# Teensy3_based_M_M_board_5x5.net
KiCad netlist of a schematic drawn in EAGLE
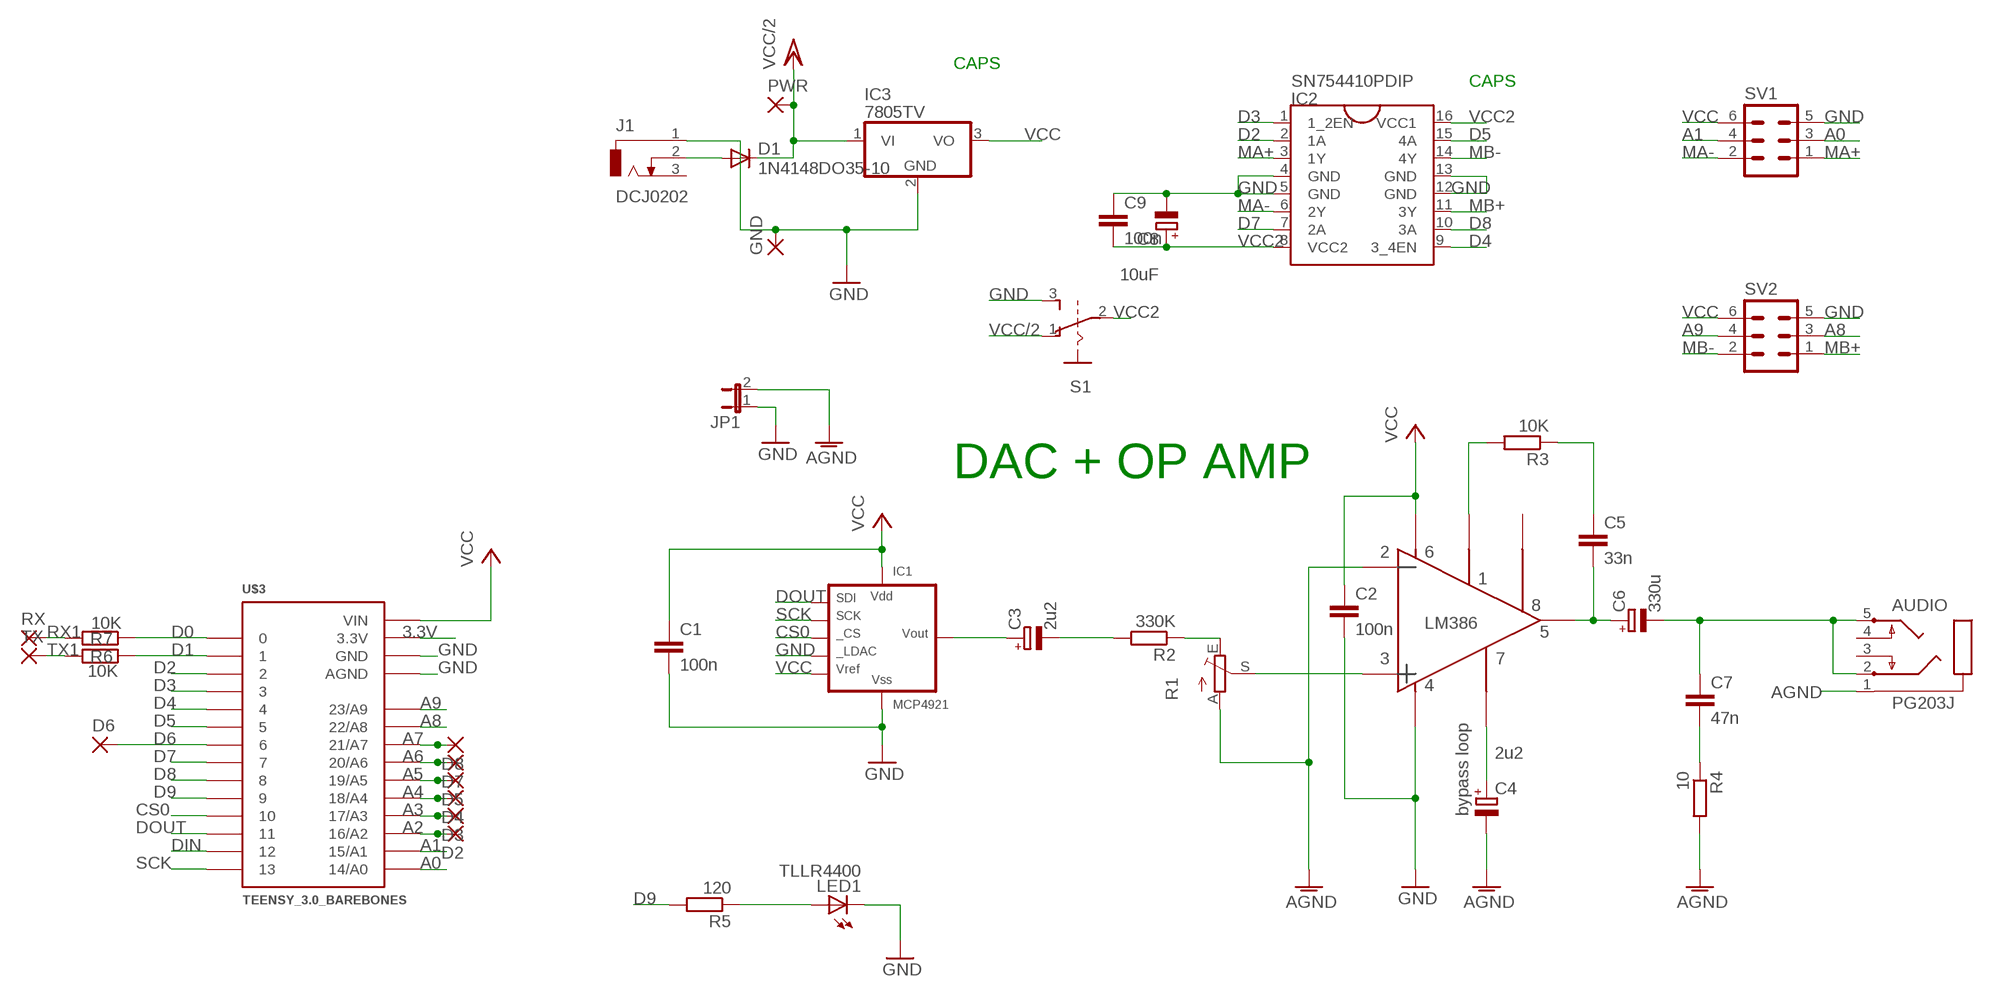
[diagram p0: schematic, sheet 1]

(export (version "E")
  (design (tool "Eeschema 10.0.6"))
  (components
    (comp (ref "AUDIO")
      (value "PG203J")
      (footprint "eagle-import:PG203J")
      (libsource (lib "eagle-import") (part "PG203J"))
    )
    (comp (ref "C1")
      (value "100n")
      (footprint "eagle-import:C050-030X075")
      (libsource (lib "eagle-import") (part "C-EU050-030X075"))
    )
    (comp (ref "C2")
      (value "100n")
      (footprint "eagle-import:C050-030X075")
      (libsource (lib "eagle-import") (part "C-EU050-030X075"))
    )
    (comp (ref "C3")
      (value "2u2")
      (footprint "eagle-import:E2-5")
      (libsource (lib "eagle-import") (part "CPOL-EUE2-5"))
    )
    (comp (ref "C4")
      (value "2u2")
      (footprint "eagle-import:E2-5")
      (libsource (lib "eagle-import") (part "CPOL-EUE2-5"))
    )
    (comp (ref "C5")
      (value "33n")
      (footprint "eagle-import:C050-030X075")
      (libsource (lib "eagle-import") (part "C-EU050-030X075"))
    )
    (comp (ref "C6")
      (value "330u")
      (footprint "eagle-import:E2,5-7")
      (libsource (lib "eagle-import") (part "CPOL-EUE2.5-7"))
    )
    (comp (ref "C7")
      (value "47n")
      (footprint "eagle-import:C050-030X075")
      (libsource (lib "eagle-import") (part "C-EU050-030X075"))
    )
    (comp (ref "C8")
      (value "10uF")
      (footprint "eagle-import:E2-5")
      (libsource (lib "eagle-import") (part "CPOL-EUE2-5"))
    )
    (comp (ref "C9")
      (value "100n")
      (footprint "eagle-import:C050-030X075")
      (libsource (lib "eagle-import") (part "C-EU050-030X075"))
    )
    (comp (ref "D1")
      (value "1N4148DO35-10")
      (footprint "eagle-import:DO35-10")
      (libsource (lib "eagle-import") (part "1N4148DO35-10"))
    )
    (comp (ref "D2")
      (value "2,15/1,0")
      (footprint "eagle-import:2,15_1,0")
      (libsource (lib "eagle-import") (part "2,15/1,0"))
    )
    (comp (ref "D3")
      (value "2,15/1,0")
      (footprint "eagle-import:2,15_1,0")
      (libsource (lib "eagle-import") (part "2,15/1,0"))
    )
    (comp (ref "D4")
      (value "2,15/1,0")
      (footprint "eagle-import:2,15_1,0")
      (libsource (lib "eagle-import") (part "2,15/1,0"))
    )
    (comp (ref "D5")
      (value "2,15/1,0")
      (footprint "eagle-import:2,15_1,0")
      (libsource (lib "eagle-import") (part "2,15/1,0"))
    )
    (comp (ref "D6")
      (value "2,15/1,0")
      (footprint "eagle-import:2,15_1,0")
      (libsource (lib "eagle-import") (part "2,15/1,0"))
    )
    (comp (ref "D7")
      (value "2,15/1,0")
      (footprint "eagle-import:2,15_1,0")
      (libsource (lib "eagle-import") (part "2,15/1,0"))
    )
    (comp (ref "D8")
      (value "2,15/1,0")
      (footprint "eagle-import:2,15_1,0")
      (libsource (lib "eagle-import") (part "2,15/1,0"))
    )
    (comp (ref "GND")
      (value "2,15/1,0")
      (footprint "eagle-import:2,15_1,0")
      (libsource (lib "eagle-import") (part "2,15/1,0"))
    )
    (comp (ref "IC1")
      (value "MCP4921")
      (footprint "eagle-import:DIL8")
      (libsource (lib "eagle-import") (part "MCP4921P"))
    )
    (comp (ref "IC2")
      (value "SN754410PDIP")
      (footprint "eagle-import:DIL16")
      (libsource (lib "eagle-import") (part "SN754410PDIP"))
    )
    (comp (ref "IC3")
      (value "7805TV")
      (footprint "eagle-import:TO220V")
      (libsource (lib "eagle-import") (part "78TV05"))
    )
    (comp (ref "J1")
      (value "DCJ0202")
      (footprint "eagle-import:DCJ0202")
      (libsource (lib "eagle-import") (part "DCJ0202"))
    )
    (comp (ref "JP1")
      (value "JP1E")
      (footprint "eagle-import:JP1")
      (libsource (lib "eagle-import") (part "JP1E"))
    )
    (comp (ref "LED1")
      (value "TLLR4400")
      (footprint "eagle-import:LED3MM")
      (fields (field (name "MF") "VISHAY SEMICONDUCTOR"))
      (libsource (lib "eagle-import") (part "TLLR4400"))
    )
    (comp (ref "PWR")
      (value "2,15/1,0")
      (footprint "eagle-import:2,15_1,0")
      (libsource (lib "eagle-import") (part "2,15/1,0"))
    )
    (comp (ref "R1")
      (value "TRIM_EU-CA9V")
      (footprint "eagle-import:CA9V")
      (libsource (lib "eagle-import") (part "TRIM_EU-CA9V"))
    )
    (comp (ref "R2")
      (value "330K")
      (footprint "eagle-import:0207_10")
      (libsource (lib "eagle-import") (part "R-EU_0207/10"))
    )
    (comp (ref "R3")
      (value "10K")
      (footprint "eagle-import:0207_10")
      (libsource (lib "eagle-import") (part "R-EU_0207/10"))
    )
    (comp (ref "R4")
      (value "10")
      (footprint "eagle-import:0207_10")
      (libsource (lib "eagle-import") (part "R-EU_0207/10"))
    )
    (comp (ref "R5")
      (value "120")
      (footprint "eagle-import:0207_10")
      (libsource (lib "eagle-import") (part "R-EU_0207/10"))
    )
    (comp (ref "R6")
      (value "10K")
      (footprint "eagle-import:0207_10")
      (libsource (lib "eagle-import") (part "R-EU_0207/10"))
    )
    (comp (ref "R7")
      (value "10K")
      (footprint "eagle-import:0207_10")
      (libsource (lib "eagle-import") (part "R-EU_0207/10"))
    )
    (comp (ref "RX")
      (value "2,15/1,0")
      (footprint "eagle-import:2,15_1,0")
      (libsource (lib "eagle-import") (part "2,15/1,0"))
    )
    (comp (ref "S1")
      (value "EG1218")
      (footprint "eagle-import:GF-126-0159")
      (libsource (lib "eagle-import") (part "EG1218"))
    )
    (comp (ref "SV1")
      (value "ML6")
      (footprint "eagle-import:ML6")
      (libsource (lib "eagle-import") (part "ML6"))
    )
    (comp (ref "SV2")
      (value "ML6")
      (footprint "eagle-import:ML6")
      (libsource (lib "eagle-import") (part "ML6"))
    )
    (comp (ref "TX")
      (value "2,15/1,0")
      (footprint "eagle-import:2,15_1,0")
      (libsource (lib "eagle-import") (part "2,15/1,0"))
    )
    (comp (ref "U$2")
      (value "LM386")
      (footprint "eagle-import:LM386")
      (libsource (lib "eagle-import") (part "LM386OA"))
    )
    (comp (ref "U$3")
      (value "TEENSY_3.0_BAREBONES")
      (footprint "eagle-import:TEENSY_3.0_BAREBONES")
      (libsource (lib "eagle-import") (part "TEENSY_3.0_BAREBONES"))
    )
  )
  (nets
    (net (code "1") (name "/3.3V") (class "Default")
      (node (ref "U$3") (pin "3.3V") (pinfunction "3.3V_3.3V") (pintype "power_in"))
    )
    (net (code "2") (name "/A0") (class "Default")
      (node (ref "SV1") (pin "3") (pinfunction "3_3") (pintype "passive"))
      (node (ref "U$3") (pin "14/A0") (pinfunction "14/A0_14/A0") (pintype "bidirectional"))
    )
    (net (code "3") (name "/A1") (class "Default")
      (node (ref "SV1") (pin "4") (pinfunction "4_4") (pintype "passive"))
      (node (ref "U$3") (pin "15/A1") (pinfunction "15/A1_15/A1") (pintype "bidirectional"))
    )
    (net (code "4") (name "/A2") (class "Default")
      (node (ref "D2") (pin "1") (pinfunction "P_1") (pintype "passive"))
      (node (ref "U$3") (pin "16/A2") (pinfunction "16/A2_16/A2") (pintype "bidirectional"))
    )
    (net (code "5") (name "/A3") (class "Default")
      (node (ref "D3") (pin "1") (pinfunction "P_1") (pintype "passive"))
      (node (ref "U$3") (pin "17/A3") (pinfunction "17/A3_17/A3") (pintype "bidirectional"))
    )
    (net (code "6") (name "/A4") (class "Default")
      (node (ref "D4") (pin "1") (pinfunction "P_1") (pintype "passive"))
      (node (ref "U$3") (pin "18/A4") (pinfunction "18/A4_18/A4") (pintype "bidirectional"))
    )
    (net (code "7") (name "/A5") (class "Default")
      (node (ref "D5") (pin "1") (pinfunction "P_1") (pintype "passive"))
      (node (ref "U$3") (pin "19/A5") (pinfunction "19/A5_19/A5") (pintype "bidirectional"))
    )
    (net (code "8") (name "/A6") (class "Default")
      (node (ref "D7") (pin "1") (pinfunction "P_1") (pintype "passive"))
      (node (ref "U$3") (pin "20/A6") (pinfunction "20/A6_20/A6") (pintype "bidirectional"))
    )
    (net (code "9") (name "/A7") (class "Default")
      (node (ref "D8") (pin "1") (pinfunction "P_1") (pintype "passive"))
      (node (ref "U$3") (pin "21/A7") (pinfunction "21/A7_21/A7") (pintype "bidirectional"))
    )
    (net (code "10") (name "/A8") (class "Default")
      (node (ref "SV2") (pin "3") (pinfunction "3_3") (pintype "passive"))
      (node (ref "U$3") (pin "22/A8") (pinfunction "22/A8_22/A8") (pintype "bidirectional"))
    )
    (net (code "11") (name "/A9") (class "Default")
      (node (ref "SV2") (pin "4") (pinfunction "4_4") (pintype "passive"))
      (node (ref "U$3") (pin "23/A9") (pinfunction "23/A9_23/A9") (pintype "bidirectional"))
    )
    (net (code "12") (name "/CS0") (class "Default")
      (node (ref "IC1") (pin "2") (pinfunction "CS_2") (pintype "input"))
      (node (ref "U$3") (pin "10") (pinfunction "10_10") (pintype "bidirectional"))
    )
    (net (code "13") (name "/D0") (class "Default")
      (node (ref "R7") (pin "1") (pinfunction "1_1") (pintype "passive"))
      (node (ref "U$3") (pin "0") (pinfunction "0_0") (pintype "bidirectional"))
    )
    (net (code "14") (name "/D1") (class "Default")
      (node (ref "R6") (pin "1") (pinfunction "1_1") (pintype "passive"))
      (node (ref "U$3") (pin "1") (pinfunction "1_1") (pintype "bidirectional"))
    )
    (net (code "15") (name "/D2") (class "Default")
      (node (ref "IC2") (pin "2") (pinfunction "1A_2") (pintype "bidirectional"))
      (node (ref "U$3") (pin "2") (pinfunction "2_2") (pintype "bidirectional"))
    )
    (net (code "16") (name "/D3") (class "Default")
      (node (ref "IC2") (pin "1") (pinfunction "1_2EN_1") (pintype "bidirectional"))
      (node (ref "U$3") (pin "3") (pinfunction "3_3") (pintype "bidirectional"))
    )
    (net (code "17") (name "/D4") (class "Default")
      (node (ref "IC2") (pin "9") (pinfunction "3_4EN_9") (pintype "bidirectional"))
      (node (ref "U$3") (pin "4") (pinfunction "4_4") (pintype "bidirectional"))
    )
    (net (code "18") (name "/D5") (class "Default")
      (node (ref "IC2") (pin "15") (pinfunction "4A_15") (pintype "bidirectional"))
      (node (ref "U$3") (pin "5") (pinfunction "5_5") (pintype "bidirectional"))
    )
    (net (code "19") (name "/D6") (class "Default")
      (node (ref "D6") (pin "1") (pinfunction "P_1") (pintype "passive"))
      (node (ref "U$3") (pin "6") (pinfunction "6_6") (pintype "bidirectional"))
    )
    (net (code "20") (name "/D7") (class "Default")
      (node (ref "IC2") (pin "7") (pinfunction "2A_7") (pintype "bidirectional"))
      (node (ref "U$3") (pin "7") (pinfunction "7_7") (pintype "bidirectional"))
    )
    (net (code "21") (name "/D8") (class "Default")
      (node (ref "IC2") (pin "10") (pinfunction "3A_10") (pintype "bidirectional"))
      (node (ref "U$3") (pin "8") (pinfunction "8_8") (pintype "bidirectional"))
    )
    (net (code "22") (name "/D9") (class "Default")
      (node (ref "R5") (pin "2") (pinfunction "2_2") (pintype "passive"))
      (node (ref "U$3") (pin "9") (pinfunction "9_9") (pintype "bidirectional"))
    )
    (net (code "23") (name "/DIN") (class "Default")
      (node (ref "U$3") (pin "12") (pinfunction "12_12") (pintype "bidirectional"))
    )
    (net (code "24") (name "/DOUT") (class "Default")
      (node (ref "IC1") (pin "4") (pinfunction "SDI_4") (pintype "input"))
      (node (ref "U$3") (pin "11") (pinfunction "11_11") (pintype "bidirectional"))
    )
    (net (code "25") (name "/MA+") (class "Default")
      (node (ref "IC2") (pin "3") (pinfunction "1Y_3") (pintype "bidirectional"))
      (node (ref "SV1") (pin "1") (pinfunction "1_1") (pintype "passive"))
    )
    (net (code "26") (name "/MA-") (class "Default")
      (node (ref "IC2") (pin "6") (pinfunction "2Y_6") (pintype "bidirectional"))
      (node (ref "SV1") (pin "2") (pinfunction "2_2") (pintype "passive"))
    )
    (net (code "27") (name "/MB+") (class "Default")
      (node (ref "IC2") (pin "11") (pinfunction "3Y_11") (pintype "bidirectional"))
      (node (ref "SV2") (pin "1") (pinfunction "1_1") (pintype "passive"))
    )
    (net (code "28") (name "/MB-") (class "Default")
      (node (ref "IC2") (pin "14") (pinfunction "4Y_14") (pintype "bidirectional"))
      (node (ref "SV2") (pin "2") (pinfunction "2_2") (pintype "passive"))
    )
    (net (code "29") (name "/RX1") (class "Default")
      (node (ref "R7") (pin "2") (pinfunction "2_2") (pintype "passive"))
      (node (ref "RX") (pin "1") (pinfunction "P_1") (pintype "passive"))
    )
    (net (code "30") (name "/SCK") (class "Default")
      (node (ref "IC1") (pin "3") (pinfunction "SCK_3") (pintype "input"))
      (node (ref "U$3") (pin "13") (pinfunction "13_13") (pintype "bidirectional"))
    )
    (net (code "31") (name "/TX1") (class "Default")
      (node (ref "R6") (pin "2") (pinfunction "2_2") (pintype "passive"))
      (node (ref "TX") (pin "1") (pinfunction "P_1") (pintype "passive"))
    )
    (net (code "32") (name "/VCC2") (class "Default")
      (node (ref "C8") (pin "+") (pinfunction "+_+") (pintype "passive"))
      (node (ref "C9") (pin "2") (pinfunction "2_2") (pintype "passive"))
      (node (ref "IC2") (pin "16") (pinfunction "VCC1_16") (pintype "bidirectional"))
      (node (ref "IC2") (pin "8") (pinfunction "VCC2_8") (pintype "bidirectional"))
      (node (ref "S1") (pin "2") (pinfunction "02_2") (pintype "passive"))
    )
    (net (code "33") (name "AGND") (class "Default")
      (node (ref "AUDIO") (pin "1") (pinfunction "1_1") (pintype "passive"))
      (node (ref "C4") (pin "-") (pinfunction "-_-") (pintype "passive"))
      (node (ref "JP1") (pin "2") (pinfunction "2_2") (pintype "passive"))
      (node (ref "R1") (pin "A") (pinfunction "A_A") (pintype "passive"))
      (node (ref "R4") (pin "2") (pinfunction "2_2") (pintype "passive"))
      (node (ref "U$2") (pin "2") (pinfunction "P$2_2") (pintype "bidirectional"))
    )
    (net (code "34") (name "GND") (class "Default")
      (node (ref "C1") (pin "2") (pinfunction "2_2") (pintype "passive"))
      (node (ref "C2") (pin "2") (pinfunction "2_2") (pintype "passive"))
      (node (ref "C8") (pin "-") (pinfunction "-_-") (pintype "passive"))
      (node (ref "C9") (pin "1") (pinfunction "1_1") (pintype "passive"))
      (node (ref "GND") (pin "1") (pinfunction "P_1") (pintype "passive"))
      (node (ref "IC1") (pin "5") (pinfunction "LDAC_5") (pintype "input"))
      (node (ref "IC1") (pin "7") (pinfunction "VSS_7") (pintype "power_in"))
      (node (ref "IC2") (pin "12") (pinfunction "GND_12") (pintype "bidirectional"))
      (node (ref "IC2") (pin "13") (pinfunction "GND_13") (pintype "bidirectional"))
      (node (ref "IC2") (pin "4") (pinfunction "GND_4") (pintype "bidirectional"))
      (node (ref "IC2") (pin "5") (pinfunction "GND_5") (pintype "bidirectional"))
      (node (ref "IC3") (pin "2") (pinfunction "GND_2") (pintype "passive"))
      (node (ref "J1") (pin "1") (pinfunction "1_1") (pintype "passive"))
      (node (ref "JP1") (pin "1") (pinfunction "1_1") (pintype "passive"))
      (node (ref "LED1") (pin "K") (pinfunction "C_K") (pintype "passive"))
      (node (ref "S1") (pin "3") (pinfunction "3_3") (pintype "passive"))
      (node (ref "SV1") (pin "5") (pinfunction "5_5") (pintype "passive"))
      (node (ref "SV2") (pin "5") (pinfunction "5_5") (pintype "passive"))
      (node (ref "U$2") (pin "4") (pinfunction "P$4_4") (pintype "bidirectional"))
      (node (ref "U$3") (pin "AGND") (pinfunction "AGND_AGND") (pintype "power_in"))
      (node (ref "U$3") (pin "GND") (pinfunction "GND_GND") (pintype "power_in"))
    )
    (net (code "35") (name "Net-(AUDIO-Pad2)") (class "Default")
      (node (ref "AUDIO") (pin "2") (pinfunction "2_2") (pintype "passive"))
      (node (ref "AUDIO") (pin "5") (pinfunction "5_5") (pintype "passive"))
      (node (ref "C6") (pin "-") (pinfunction "-_-") (pintype "passive"))
      (node (ref "C7") (pin "1") (pinfunction "1_1") (pintype "passive"))
    )
    (net (code "36") (name "Net-(C3-Pad-)") (class "Default")
      (node (ref "C3") (pin "-") (pinfunction "-_-") (pintype "passive"))
      (node (ref "R2") (pin "2") (pinfunction "2_2") (pintype "passive"))
    )
    (net (code "37") (name "Net-(C5-Pad1)") (class "Default")
      (node (ref "C5") (pin "1") (pinfunction "1_1") (pintype "passive"))
      (node (ref "R3") (pin "1") (pinfunction "1_1") (pintype "passive"))
    )
    (net (code "38") (name "Net-(C7-Pad2)") (class "Default")
      (node (ref "C7") (pin "2") (pinfunction "2_2") (pintype "passive"))
      (node (ref "R4") (pin "1") (pinfunction "1_1") (pintype "passive"))
    )
    (net (code "39") (name "Net-(D1-PadA)") (class "Default")
      (node (ref "D1") (pin "A") (pinfunction "A_A") (pintype "passive"))
      (node (ref "J1") (pin "2") (pinfunction "2_2") (pintype "passive"))
    )
    (net (code "40") (name "Net-(IC1-VOUT)") (class "Default")
      (node (ref "C3") (pin "+") (pinfunction "+_+") (pintype "passive"))
      (node (ref "IC1") (pin "8") (pinfunction "VOUT_8") (pintype "output"))
    )
    (net (code "41") (name "Net-(LED1-PadA)") (class "Default")
      (node (ref "LED1") (pin "A") (pinfunction "A_A") (pintype "passive"))
      (node (ref "R5") (pin "1") (pinfunction "1_1") (pintype "passive"))
    )
    (net (code "42") (name "Net-(R1-PadE)") (class "Default")
      (node (ref "R1") (pin "E") (pinfunction "E_E") (pintype "passive"))
      (node (ref "R2") (pin "1") (pinfunction "1_1") (pintype "passive"))
    )
    (net (code "43") (name "Net-(U$2-P$1)") (class "Default")
      (node (ref "R3") (pin "2") (pinfunction "2_2") (pintype "passive"))
      (node (ref "U$2") (pin "1") (pinfunction "P$1_1") (pintype "bidirectional"))
    )
    (net (code "44") (name "Net-(U$2-P$3)") (class "Default")
      (node (ref "R1") (pin "S") (pinfunction "S_S") (pintype "passive"))
      (node (ref "U$2") (pin "3") (pinfunction "P$3_3") (pintype "bidirectional"))
    )
    (net (code "45") (name "Net-(U$2-P$5)") (class "Default")
      (node (ref "C5") (pin "2") (pinfunction "2_2") (pintype "passive"))
      (node (ref "C6") (pin "+") (pinfunction "+_+") (pintype "passive"))
      (node (ref "U$2") (pin "5") (pinfunction "P$5_5") (pintype "bidirectional"))
    )
    (net (code "46") (name "Net-(U$2-P$7)") (class "Default")
      (node (ref "C4") (pin "+") (pinfunction "+_+") (pintype "passive"))
      (node (ref "U$2") (pin "7") (pinfunction "P$7_7") (pintype "bidirectional"))
    )
    (net (code "47") (name "VCC") (class "Default")
      (node (ref "C1") (pin "1") (pinfunction "1_1") (pintype "passive"))
      (node (ref "C2") (pin "1") (pinfunction "1_1") (pintype "passive"))
      (node (ref "IC1") (pin "1") (pinfunction "VDD_1") (pintype "power_in"))
      (node (ref "IC1") (pin "6") (pinfunction "VREF_6") (pintype "input"))
      (node (ref "IC3") (pin "3") (pinfunction "VO_3") (pintype "passive"))
      (node (ref "SV1") (pin "6") (pinfunction "6_6") (pintype "passive"))
      (node (ref "SV2") (pin "6") (pinfunction "6_6") (pintype "passive"))
      (node (ref "U$2") (pin "6") (pinfunction "P$6_6") (pintype "bidirectional"))
      (node (ref "U$3") (pin "VIN") (pinfunction "VIN_VIN") (pintype "power_in"))
    )
    (net (code "48") (name "VCC{slash}2") (class "Default")
      (node (ref "D1") (pin "C") (pinfunction "C_C") (pintype "passive"))
      (node (ref "IC3") (pin "1") (pinfunction "VI_1") (pintype "input"))
      (node (ref "PWR") (pin "1") (pinfunction "P_1") (pintype "passive"))
      (node (ref "S1") (pin "1") (pinfunction "1_1") (pintype "passive"))
    )
    (net (code "49") (name "unconnected-(AUDIO-Pad3)") (class "Default")
      (node (ref "AUDIO") (pin "3") (pinfunction "3_3") (pintype "passive"))
    )
    (net (code "50") (name "unconnected-(AUDIO-Pad4)") (class "Default")
      (node (ref "AUDIO") (pin "4") (pinfunction "4_4") (pintype "passive"))
    )
    (net (code "51") (name "unconnected-(J1-Pad3)") (class "Default")
      (node (ref "J1") (pin "3") (pinfunction "3_3") (pintype "passive"))
    )
    (net (code "52") (name "unconnected-(U$2-P$8-Pad8)") (class "Default")
      (node (ref "U$2") (pin "8") (pinfunction "P$8_8") (pintype "bidirectional"))
    )
  )
)
